# 3_DDR3.net
KiCad netlist of a schematic drawn in Altium Designer
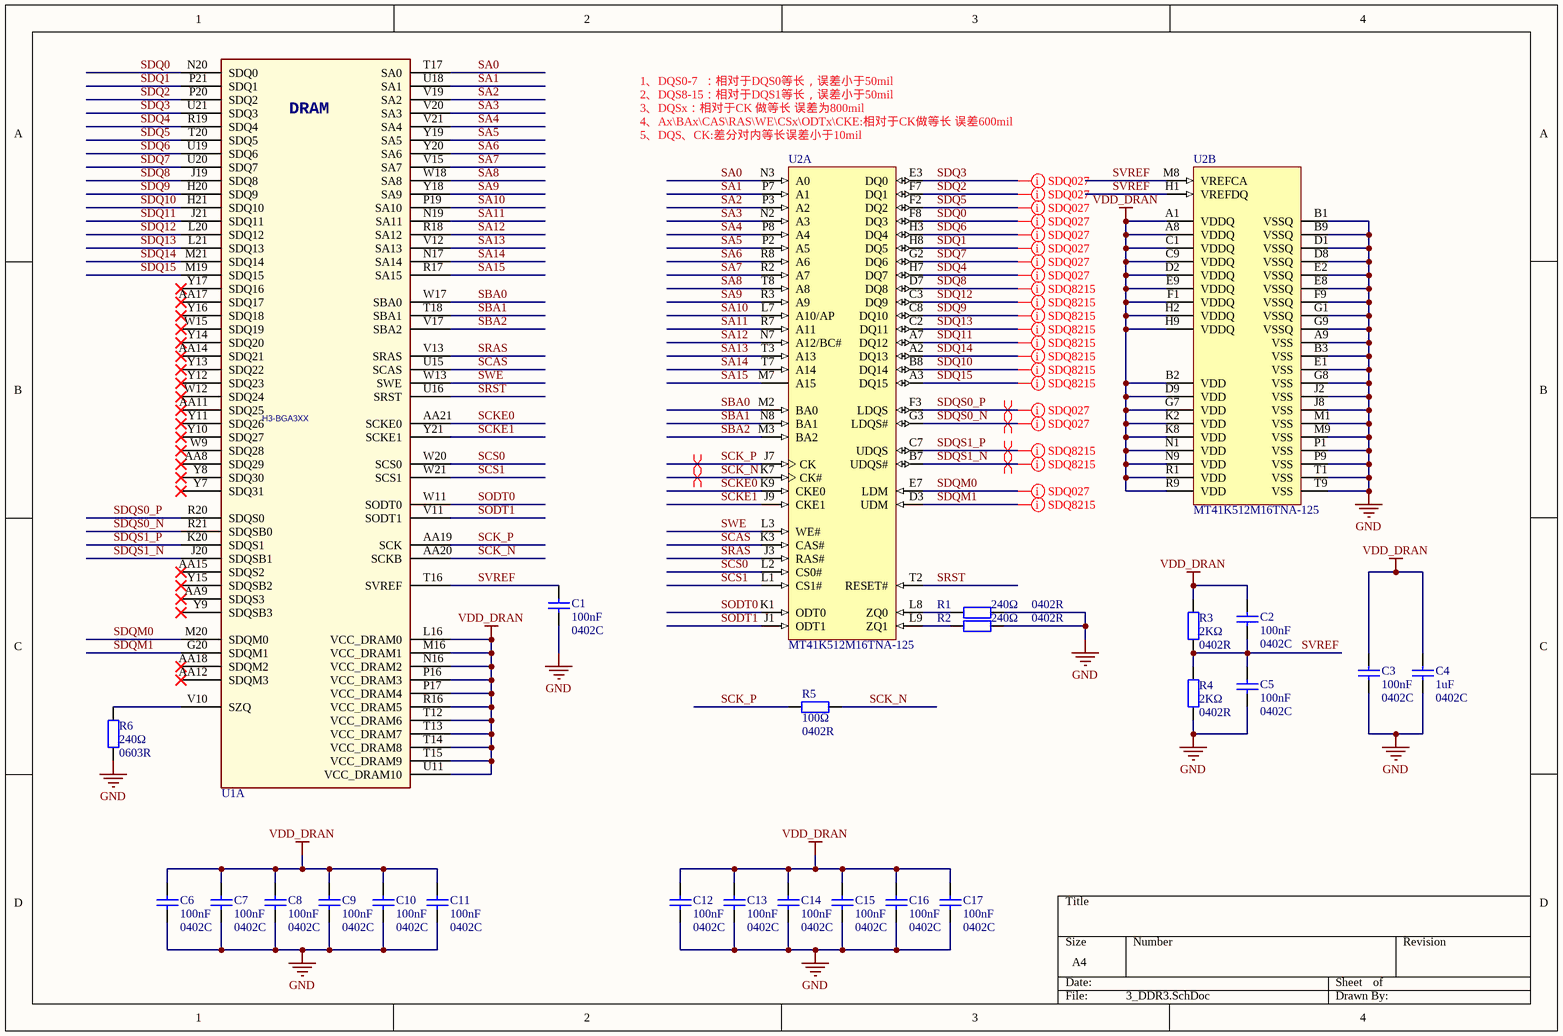
[diagram p0: 3_DDR3.SchDoc]

(export (version "E")
  (design (tool "Eeschema 10.0.6"))
  (components
    (comp (ref "C1")
      (value "100nF")
      (footprint "0402_C")
      (description "贴片电容")
      (fields (field (name "PACKAGE") "0402C"))
      (libsource (lib "Miscellaneous Devices LC") (part "0402 1nF (102) 10% 50V"))
    )
    (comp (ref "C2")
      (value "100nF")
      (footprint "0402_C")
      (description "贴片电容")
      (fields (field (name "PACKAGE") "0402C"))
      (libsource (lib "Miscellaneous Devices LC") (part "0402 1nF (102) 10% 50V"))
    )
    (comp (ref "C3")
      (value "100nF")
      (footprint "0402_C")
      (description "贴片电容")
      (fields (field (name "PACKAGE") "0402C"))
      (libsource (lib "Miscellaneous Devices LC") (part "0402 1nF (102) 10% 50V"))
    )
    (comp (ref "C4")
      (value "1uF")
      (footprint "0402_C")
      (description "贴片电容")
      (fields (field (name "PACKAGE") "0402C"))
      (libsource (lib "Miscellaneous Devices LC") (part "0402 1nF (102) 10% 50V"))
    )
    (comp (ref "C5")
      (value "100nF")
      (footprint "0402_C")
      (description "贴片电容")
      (fields (field (name "PACKAGE") "0402C"))
      (libsource (lib "Miscellaneous Devices LC") (part "0402 1nF (102) 10% 50V"))
    )
    (comp (ref "C6")
      (value "100nF")
      (footprint "0402_C")
      (description "贴片电容")
      (fields (field (name "PACKAGE") "0402C"))
      (libsource (lib "Miscellaneous Devices LC") (part "0402 1nF (102) 10% 50V"))
    )
    (comp (ref "C7")
      (value "100nF")
      (footprint "0402_C")
      (description "贴片电容")
      (fields (field (name "PACKAGE") "0402C"))
      (libsource (lib "Miscellaneous Devices LC") (part "0402 1nF (102) 10% 50V"))
    )
    (comp (ref "C8")
      (value "100nF")
      (footprint "0402_C")
      (description "贴片电容")
      (fields (field (name "PACKAGE") "0402C"))
      (libsource (lib "Miscellaneous Devices LC") (part "0402 1nF (102) 10% 50V"))
    )
    (comp (ref "C9")
      (value "100nF")
      (footprint "0402_C")
      (description "贴片电容")
      (fields (field (name "PACKAGE") "0402C"))
      (libsource (lib "Miscellaneous Devices LC") (part "0402 1nF (102) 10% 50V"))
    )
    (comp (ref "C10")
      (value "100nF")
      (footprint "0402_C")
      (description "贴片电容")
      (fields (field (name "PACKAGE") "0402C"))
      (libsource (lib "Miscellaneous Devices LC") (part "0402 1nF (102) 10% 50V"))
    )
    (comp (ref "C11")
      (value "100nF")
      (footprint "0402_C")
      (description "贴片电容")
      (fields (field (name "PACKAGE") "0402C"))
      (libsource (lib "Miscellaneous Devices LC") (part "0402 1nF (102) 10% 50V"))
    )
    (comp (ref "C12")
      (value "100nF")
      (footprint "0402_C")
      (description "贴片电容")
      (fields (field (name "PACKAGE") "0402C"))
      (libsource (lib "Miscellaneous Devices LC") (part "0402 1nF (102) 10% 50V"))
    )
    (comp (ref "C13")
      (value "100nF")
      (footprint "0402_C")
      (description "贴片电容")
      (fields (field (name "PACKAGE") "0402C"))
      (libsource (lib "Miscellaneous Devices LC") (part "0402 1nF (102) 10% 50V"))
    )
    (comp (ref "C14")
      (value "100nF")
      (footprint "0402_C")
      (description "贴片电容")
      (fields (field (name "PACKAGE") "0402C"))
      (libsource (lib "Miscellaneous Devices LC") (part "0402 1nF (102) 10% 50V"))
    )
    (comp (ref "C15")
      (value "100nF")
      (footprint "0402_C")
      (description "贴片电容")
      (fields (field (name "PACKAGE") "0402C"))
      (libsource (lib "Miscellaneous Devices LC") (part "0402 1nF (102) 10% 50V"))
    )
    (comp (ref "C16")
      (value "100nF")
      (footprint "0402_C")
      (description "贴片电容")
      (fields (field (name "PACKAGE") "0402C"))
      (libsource (lib "Miscellaneous Devices LC") (part "0402 1nF (102) 10% 50V"))
    )
    (comp (ref "C17")
      (value "100nF")
      (footprint "0402_C")
      (description "贴片电容")
      (fields (field (name "PACKAGE") "0402C"))
      (libsource (lib "Miscellaneous Devices LC") (part "0402 1nF (102) 10% 50V"))
    )
    (comp (ref "R1")
      (value "240Ω")
      (footprint "0402_R")
      (description "贴片电阻")
      (fields (field (name "PACKAGE") "0402R"))
      (libsource (lib "") (part "0402 1KΩ (1001) 1%_1"))
    )
    (comp (ref "R2")
      (value "240Ω")
      (footprint "0402_R")
      (description "贴片电阻")
      (fields (field (name "PACKAGE") "0402R"))
      (libsource (lib "") (part "0402 1KΩ (1001) 1%_1"))
    )
    (comp (ref "R3")
      (value "2KΩ")
      (footprint "0402_R")
      (description "贴片电阻")
      (fields (field (name "PACKAGE") "0402R"))
      (libsource (lib "Miscellaneous Devices LC") (part "0402 1KΩ (1001) 1%"))
    )
    (comp (ref "R4")
      (value "2KΩ")
      (footprint "0402_R")
      (description "贴片电阻")
      (fields (field (name "PACKAGE") "0402R"))
      (libsource (lib "Miscellaneous Devices LC") (part "0402 1KΩ (1001) 1%"))
    )
    (comp (ref "R5")
      (value "100Ω")
      (footprint "0402_R")
      (description "贴片电阻")
      (fields (field (name "PACKAGE") "0402R"))
      (libsource (lib "") (part "0402 1KΩ (1001) 1%_1"))
    )
    (comp (ref "R6")
      (value "240Ω")
      (footprint "0603_R")
      (description "贴片电阻")
      (fields (field (name "PACKAGE") "0603R"))
      (libsource (lib "") (part "0402 1KΩ (1001) 1%_2"))
    )
    (comp (ref "U1")
      (value "H3-BGA3XX")
      (footprint "BGA347P0_65B14X14")
      (libsource (lib "MAGNET_L") (part "H3-BGA3XX"))
    )
    (comp (ref "U2")
      (value "MT41K512M16TNA-125")
      (footprint "MICT-TNA-96")
      (description "8Gb SDRAM, 512Mb x 16, 1.25ns, 1.35V, 0 to 95 degC, 96-Ball FBGA, Pb-Free")
      (fields (field (name "VOLTAGE") "1.35V?") (field (name "MANUFACTURER") "Micron"))
      (libsource (lib "Micron Memory DDR3 SDRAM") (part "MT41K512M16TNA-125"))
    )
  )
  (nets
    (net (code "1") (name "/SA0") (class "Default")
      (node (ref "U1") (pin "T17") (pinfunction "SA0_T17") (pintype "passive"))
      (node (ref "U2") (pin "N3") (pinfunction "A0_N3") (pintype "input"))
    )
    (net (code "2") (name "/SA1") (class "Default")
      (node (ref "U1") (pin "U18") (pinfunction "SA1_U18") (pintype "passive"))
      (node (ref "U2") (pin "P7") (pinfunction "A1_P7") (pintype "input"))
    )
    (net (code "3") (name "/SA2") (class "Default")
      (node (ref "U1") (pin "V19") (pinfunction "SA2_V19") (pintype "passive"))
      (node (ref "U2") (pin "P3") (pinfunction "A2_P3") (pintype "input"))
    )
    (net (code "4") (name "/SA3") (class "Default")
      (node (ref "U1") (pin "V20") (pinfunction "SA3_V20") (pintype "passive"))
      (node (ref "U2") (pin "N2") (pinfunction "A3_N2") (pintype "input"))
    )
    (net (code "5") (name "/SA4") (class "Default")
      (node (ref "U1") (pin "V21") (pinfunction "SA4_V21") (pintype "passive"))
      (node (ref "U2") (pin "P8") (pinfunction "A4_P8") (pintype "input"))
    )
    (net (code "6") (name "/SA5") (class "Default")
      (node (ref "U1") (pin "Y19") (pinfunction "SA5_Y19") (pintype "passive"))
      (node (ref "U2") (pin "P2") (pinfunction "A5_P2") (pintype "input"))
    )
    (net (code "7") (name "/SA6") (class "Default")
      (node (ref "U1") (pin "Y20") (pinfunction "SA6_Y20") (pintype "passive"))
      (node (ref "U2") (pin "R8") (pinfunction "A6_R8") (pintype "input"))
    )
    (net (code "8") (name "/SA7") (class "Default")
      (node (ref "U1") (pin "V15") (pinfunction "SA7_V15") (pintype "passive"))
      (node (ref "U2") (pin "R2") (pinfunction "A7_R2") (pintype "input"))
    )
    (net (code "9") (name "/SA8") (class "Default")
      (node (ref "U1") (pin "W18") (pinfunction "SA8_W18") (pintype "passive"))
      (node (ref "U2") (pin "T8") (pinfunction "A8_T8") (pintype "input"))
    )
    (net (code "10") (name "/SA9") (class "Default")
      (node (ref "U1") (pin "Y18") (pinfunction "SA9_Y18") (pintype "passive"))
      (node (ref "U2") (pin "R3") (pinfunction "A9_R3") (pintype "input"))
    )
    (net (code "11") (name "/SA10") (class "Default")
      (node (ref "U1") (pin "P19") (pinfunction "SA10_P19") (pintype "passive"))
      (node (ref "U2") (pin "L7") (pinfunction "A10/AP_L7") (pintype "input"))
    )
    (net (code "12") (name "/SA11") (class "Default")
      (node (ref "U1") (pin "N19") (pinfunction "SA11_N19") (pintype "passive"))
      (node (ref "U2") (pin "R7") (pinfunction "A11_R7") (pintype "input"))
    )
    (net (code "13") (name "/SA12") (class "Default")
      (node (ref "U1") (pin "R18") (pinfunction "SA12_R18") (pintype "passive"))
      (node (ref "U2") (pin "N7") (pinfunction "A12/BC#_N7") (pintype "input"))
    )
    (net (code "14") (name "/SA13") (class "Default")
      (node (ref "U1") (pin "V12") (pinfunction "SA13_V12") (pintype "passive"))
      (node (ref "U2") (pin "T3") (pinfunction "A13_T3") (pintype "input"))
    )
    (net (code "15") (name "/SA14") (class "Default")
      (node (ref "U1") (pin "N17") (pinfunction "SA14_N17") (pintype "passive"))
      (node (ref "U2") (pin "T7") (pinfunction "A14_T7") (pintype "input"))
    )
    (net (code "16") (name "/SA15") (class "Default")
      (node (ref "U1") (pin "R17") (pinfunction "SA15_R17") (pintype "passive"))
      (node (ref "U2") (pin "M7") (pinfunction "A15_M7") (pintype "passive"))
    )
    (net (code "17") (name "/SBA0") (class "Default")
      (node (ref "U1") (pin "W17") (pinfunction "SBA0_W17") (pintype "passive"))
      (node (ref "U2") (pin "M2") (pinfunction "BA0_M2") (pintype "input"))
    )
    (net (code "18") (name "/SBA1") (class "Default")
      (node (ref "U1") (pin "T18") (pinfunction "SBA1_T18") (pintype "passive"))
      (node (ref "U2") (pin "N8") (pinfunction "BA1_N8") (pintype "input"))
    )
    (net (code "19") (name "/SBA2") (class "Default")
      (node (ref "U1") (pin "V17") (pinfunction "SBA2_V17") (pintype "passive"))
      (node (ref "U2") (pin "M3") (pinfunction "BA2_M3") (pintype "input"))
    )
    (net (code "20") (name "/SCAS") (class "Default")
      (node (ref "U1") (pin "U15") (pinfunction "SCAS_U15") (pintype "passive"))
      (node (ref "U2") (pin "K3") (pinfunction "CAS#_K3") (pintype "input"))
    )
    (net (code "21") (name "/SCKE0") (class "Default")
      (node (ref "U1") (pin "AA21") (pinfunction "SCKE0_AA21") (pintype "passive"))
      (node (ref "U2") (pin "K9") (pinfunction "CKE0_K9") (pintype "input"))
    )
    (net (code "22") (name "/SCKE1") (class "Default")
      (node (ref "U1") (pin "Y21") (pinfunction "SCKE1_Y21") (pintype "passive"))
      (node (ref "U2") (pin "J9") (pinfunction "CKE1_J9") (pintype "input"))
    )
    (net (code "23") (name "/SCK_N") (class "Default")
      (node (ref "R5") (pin "1") (pinfunction "1_1") (pintype "passive"))
      (node (ref "U1") (pin "AA20") (pinfunction "SCKB_AA20") (pintype "passive"))
      (node (ref "U2") (pin "K7") (pinfunction "CK#_K7") (pintype "input"))
    )
    (net (code "24") (name "/SCK_P") (class "Default")
      (node (ref "R5") (pin "2") (pinfunction "2_2") (pintype "passive"))
      (node (ref "U1") (pin "AA19") (pinfunction "SCK_AA19") (pintype "passive"))
      (node (ref "U2") (pin "J7") (pinfunction "CK_J7") (pintype "input"))
    )
    (net (code "25") (name "/SCS0") (class "Default")
      (node (ref "U1") (pin "W20") (pinfunction "SCS0_W20") (pintype "passive"))
      (node (ref "U2") (pin "L2") (pinfunction "CS0#_L2") (pintype "input"))
    )
    (net (code "26") (name "/SCS1") (class "Default")
      (node (ref "U1") (pin "W21") (pinfunction "SCS1_W21") (pintype "passive"))
      (node (ref "U2") (pin "L1") (pinfunction "CS1#_L1") (pintype "input"))
    )
    (net (code "27") (name "/SDQ0") (class "Default")
      (node (ref "U1") (pin "N20") (pinfunction "SDQ0_N20") (pintype "passive"))
      (node (ref "U2") (pin "F8") (pinfunction "DQ3_F8") (pintype "bidirectional"))
    )
    (net (code "28") (name "/SDQ1") (class "Default")
      (node (ref "U1") (pin "P21") (pinfunction "SDQ1_P21") (pintype "passive"))
      (node (ref "U2") (pin "H8") (pinfunction "DQ5_H8") (pintype "bidirectional"))
    )
    (net (code "29") (name "/SDQ2") (class "Default")
      (node (ref "U1") (pin "P20") (pinfunction "SDQ2_P20") (pintype "passive"))
      (node (ref "U2") (pin "F7") (pinfunction "DQ1_F7") (pintype "bidirectional"))
    )
    (net (code "30") (name "/SDQ3") (class "Default")
      (node (ref "U1") (pin "U21") (pinfunction "SDQ3_U21") (pintype "passive"))
      (node (ref "U2") (pin "E3") (pinfunction "DQ0_E3") (pintype "bidirectional"))
    )
    (net (code "31") (name "/SDQ4") (class "Default")
      (node (ref "U1") (pin "R19") (pinfunction "SDQ4_R19") (pintype "passive"))
      (node (ref "U2") (pin "H7") (pinfunction "DQ7_H7") (pintype "bidirectional"))
    )
    (net (code "32") (name "/SDQ5") (class "Default")
      (node (ref "U1") (pin "T20") (pinfunction "SDQ5_T20") (pintype "passive"))
      (node (ref "U2") (pin "F2") (pinfunction "DQ2_F2") (pintype "bidirectional"))
    )
    (net (code "33") (name "/SDQ6") (class "Default")
      (node (ref "U1") (pin "U19") (pinfunction "SDQ6_U19") (pintype "passive"))
      (node (ref "U2") (pin "H3") (pinfunction "DQ4_H3") (pintype "bidirectional"))
    )
    (net (code "34") (name "/SDQ7") (class "Default")
      (node (ref "U1") (pin "U20") (pinfunction "SDQ7_U20") (pintype "passive"))
      (node (ref "U2") (pin "G2") (pinfunction "DQ6_G2") (pintype "bidirectional"))
    )
    (net (code "35") (name "/SDQ8") (class "Default")
      (node (ref "U1") (pin "J19") (pinfunction "SDQ8_J19") (pintype "passive"))
      (node (ref "U2") (pin "D7") (pinfunction "DQ8_D7") (pintype "bidirectional"))
    )
    (net (code "36") (name "/SDQ9") (class "Default")
      (node (ref "U1") (pin "H20") (pinfunction "SDQ9_H20") (pintype "passive"))
      (node (ref "U2") (pin "C8") (pinfunction "DQ10_C8") (pintype "bidirectional"))
    )
    (net (code "37") (name "/SDQ10") (class "Default")
      (node (ref "U1") (pin "H21") (pinfunction "SDQ10_H21") (pintype "passive"))
      (node (ref "U2") (pin "B8") (pinfunction "DQ14_B8") (pintype "bidirectional"))
    )
    (net (code "38") (name "/SDQ11") (class "Default")
      (node (ref "U1") (pin "J21") (pinfunction "SDQ11_J21") (pintype "passive"))
      (node (ref "U2") (pin "A7") (pinfunction "DQ12_A7") (pintype "bidirectional"))
    )
    (net (code "39") (name "/SDQ12") (class "Default")
      (node (ref "U1") (pin "L20") (pinfunction "SDQ12_L20") (pintype "passive"))
      (node (ref "U2") (pin "C3") (pinfunction "DQ9_C3") (pintype "bidirectional"))
    )
    (net (code "40") (name "/SDQ13") (class "Default")
      (node (ref "U1") (pin "L21") (pinfunction "SDQ13_L21") (pintype "passive"))
      (node (ref "U2") (pin "C2") (pinfunction "DQ11_C2") (pintype "bidirectional"))
    )
    (net (code "41") (name "/SDQ14") (class "Default")
      (node (ref "U1") (pin "M21") (pinfunction "SDQ14_M21") (pintype "passive"))
      (node (ref "U2") (pin "A2") (pinfunction "DQ13_A2") (pintype "bidirectional"))
    )
    (net (code "42") (name "/SDQ15") (class "Default")
      (node (ref "U1") (pin "M19") (pinfunction "SDQ15_M19") (pintype "passive"))
      (node (ref "U2") (pin "A3") (pinfunction "DQ15_A3") (pintype "bidirectional"))
    )
    (net (code "43") (name "/SDQM0") (class "Default")
      (node (ref "U1") (pin "M20") (pinfunction "SDQM0_M20") (pintype "passive"))
      (node (ref "U2") (pin "E7") (pinfunction "LDM_E7") (pintype "input"))
    )
    (net (code "44") (name "/SDQM1") (class "Default")
      (node (ref "U1") (pin "G20") (pinfunction "SDQM1_G20") (pintype "passive"))
      (node (ref "U2") (pin "D3") (pinfunction "UDM_D3") (pintype "input"))
    )
    (net (code "45") (name "/SDQS0_N") (class "Default")
      (node (ref "U1") (pin "R21") (pinfunction "SDQSB0_R21") (pintype "passive"))
      (node (ref "U2") (pin "G3") (pinfunction "LDQS#_G3") (pintype "bidirectional"))
    )
    (net (code "46") (name "/SDQS0_P") (class "Default")
      (node (ref "U1") (pin "R20") (pinfunction "SDQS0_R20") (pintype "passive"))
      (node (ref "U2") (pin "F3") (pinfunction "LDQS_F3") (pintype "bidirectional"))
    )
    (net (code "47") (name "/SDQS1_N") (class "Default")
      (node (ref "U1") (pin "J20") (pinfunction "SDQSB1_J20") (pintype "passive"))
      (node (ref "U2") (pin "B7") (pinfunction "UDQS#_B7") (pintype "bidirectional"))
    )
    (net (code "48") (name "/SDQS1_P") (class "Default")
      (node (ref "U1") (pin "K20") (pinfunction "SDQS1_K20") (pintype "passive"))
      (node (ref "U2") (pin "C7") (pinfunction "UDQS_C7") (pintype "bidirectional"))
    )
    (net (code "49") (name "/SODT0") (class "Default")
      (node (ref "U1") (pin "W11") (pinfunction "SODT0_W11") (pintype "passive"))
      (node (ref "U2") (pin "K1") (pinfunction "ODT0_K1") (pintype "input"))
    )
    (net (code "50") (name "/SODT1") (class "Default")
      (node (ref "U1") (pin "V11") (pinfunction "SODT1_V11") (pintype "passive"))
      (node (ref "U2") (pin "J1") (pinfunction "ODT1_J1") (pintype "input"))
    )
    (net (code "51") (name "/SRAS") (class "Default")
      (node (ref "U1") (pin "V13") (pinfunction "SRAS_V13") (pintype "passive"))
      (node (ref "U2") (pin "J3") (pinfunction "RAS#_J3") (pintype "input"))
    )
    (net (code "52") (name "/SRST") (class "Default")
      (node (ref "U1") (pin "U16") (pinfunction "SRST_U16") (pintype "passive"))
      (node (ref "U2") (pin "T2") (pinfunction "RESET#_T2") (pintype "input"))
    )
    (net (code "53") (name "/SVREF") (class "Default")
      (node (ref "C1") (pin "2") (pinfunction "2_2") (pintype "passive"))
      (node (ref "C2") (pin "1") (pinfunction "1_1") (pintype "passive"))
      (node (ref "C5") (pin "2") (pinfunction "2_2") (pintype "passive"))
      (node (ref "R3") (pin "2") (pinfunction "2_2") (pintype "passive"))
      (node (ref "R4") (pin "1") (pinfunction "1_1") (pintype "passive"))
      (node (ref "U1") (pin "T16") (pinfunction "SVREF_T16") (pintype "passive"))
      (node (ref "U2") (pin "H1") (pinfunction "VREFDQ_H1") (pintype "input"))
      (node (ref "U2") (pin "M8") (pinfunction "VREFCA_M8") (pintype "input"))
    )
    (net (code "54") (name "/SWE") (class "Default")
      (node (ref "U1") (pin "W13") (pinfunction "SWE_W13") (pintype "passive"))
      (node (ref "U2") (pin "L3") (pinfunction "WE#_L3") (pintype "input"))
    )
    (net (code "55") (name "GND") (class "Default")
      (node (ref "C1") (pin "1") (pinfunction "1_1") (pintype "passive"))
      (node (ref "C10") (pin "1") (pinfunction "1_1") (pintype "passive"))
      (node (ref "C11") (pin "1") (pinfunction "1_1") (pintype "passive"))
      (node (ref "C12") (pin "1") (pinfunction "1_1") (pintype "passive"))
      (node (ref "C13") (pin "1") (pinfunction "1_1") (pintype "passive"))
      (node (ref "C14") (pin "1") (pinfunction "1_1") (pintype "passive"))
      (node (ref "C15") (pin "1") (pinfunction "1_1") (pintype "passive"))
      (node (ref "C16") (pin "1") (pinfunction "1_1") (pintype "passive"))
      (node (ref "C17") (pin "1") (pinfunction "1_1") (pintype "passive"))
      (node (ref "C3") (pin "1") (pinfunction "1_1") (pintype "passive"))
      (node (ref "C4") (pin "1") (pinfunction "1_1") (pintype "passive"))
      (node (ref "C5") (pin "1") (pinfunction "1_1") (pintype "passive"))
      (node (ref "C6") (pin "1") (pinfunction "1_1") (pintype "passive"))
      (node (ref "C7") (pin "1") (pinfunction "1_1") (pintype "passive"))
      (node (ref "C8") (pin "1") (pinfunction "1_1") (pintype "passive"))
      (node (ref "C9") (pin "1") (pinfunction "1_1") (pintype "passive"))
      (node (ref "R1") (pin "1") (pinfunction "1_1") (pintype "passive"))
      (node (ref "R2") (pin "1") (pinfunction "1_1") (pintype "passive"))
      (node (ref "R4") (pin "2") (pinfunction "2_2") (pintype "passive"))
      (node (ref "R6") (pin "1") (pinfunction "1_1") (pintype "passive"))
      (node (ref "U2") (pin "A9") (pinfunction "VSS_A9") (pintype "power_in"))
      (node (ref "U2") (pin "B1") (pinfunction "VSSQ_B1") (pintype "power_in"))
      (node (ref "U2") (pin "B3") (pinfunction "VSS_B3") (pintype "power_in"))
      (node (ref "U2") (pin "B9") (pinfunction "VSSQ_B9") (pintype "power_in"))
      (node (ref "U2") (pin "D1") (pinfunction "VSSQ_D1") (pintype "power_in"))
      (node (ref "U2") (pin "D8") (pinfunction "VSSQ_D8") (pintype "power_in"))
      (node (ref "U2") (pin "E1") (pinfunction "VSS_E1") (pintype "power_in"))
      (node (ref "U2") (pin "E2") (pinfunction "VSSQ_E2") (pintype "power_in"))
      (node (ref "U2") (pin "E8") (pinfunction "VSSQ_E8") (pintype "power_in"))
      (node (ref "U2") (pin "F9") (pinfunction "VSSQ_F9") (pintype "power_in"))
      (node (ref "U2") (pin "G1") (pinfunction "VSSQ_G1") (pintype "power_in"))
      (node (ref "U2") (pin "G8") (pinfunction "VSS_G8") (pintype "power_in"))
      (node (ref "U2") (pin "G9") (pinfunction "VSSQ_G9") (pintype "power_in"))
      (node (ref "U2") (pin "J2") (pinfunction "VSS_J2") (pintype "power_in"))
      (node (ref "U2") (pin "J8") (pinfunction "VSS_J8") (pintype "power_in"))
      (node (ref "U2") (pin "M1") (pinfunction "VSS_M1") (pintype "power_in"))
      (node (ref "U2") (pin "M9") (pinfunction "VSS_M9") (pintype "power_in"))
      (node (ref "U2") (pin "P1") (pinfunction "VSS_P1") (pintype "power_in"))
      (node (ref "U2") (pin "P9") (pinfunction "VSS_P9") (pintype "power_in"))
      (node (ref "U2") (pin "T1") (pinfunction "VSS_T1") (pintype "power_in"))
      (node (ref "U2") (pin "T9") (pinfunction "VSS_T9") (pintype "power_in"))
    )
    (net (code "56") (name "Net-(U1A-SZQ)") (class "Default")
      (node (ref "R6") (pin "2") (pinfunction "2_2") (pintype "passive"))
      (node (ref "U1") (pin "V10") (pinfunction "SZQ_V10") (pintype "passive"))
    )
    (net (code "57") (name "Net-(U2A-ZQ0)") (class "Default")
      (node (ref "R1") (pin "2") (pinfunction "2_2") (pintype "passive"))
      (node (ref "U2") (pin "L8") (pinfunction "ZQ0_L8") (pintype "input"))
    )
    (net (code "58") (name "Net-(U2A-ZQ1)") (class "Default")
      (node (ref "R2") (pin "2") (pinfunction "2_2") (pintype "passive"))
      (node (ref "U2") (pin "L9") (pinfunction "ZQ1_L9") (pintype "input"))
    )
    (net (code "59") (name "VDD_DRAN") (class "Default")
      (node (ref "C10") (pin "2") (pinfunction "2_2") (pintype "passive"))
      (node (ref "C11") (pin "2") (pinfunction "2_2") (pintype "passive"))
      (node (ref "C12") (pin "2") (pinfunction "2_2") (pintype "passive"))
      (node (ref "C13") (pin "2") (pinfunction "2_2") (pintype "passive"))
      (node (ref "C14") (pin "2") (pinfunction "2_2") (pintype "passive"))
      (node (ref "C15") (pin "2") (pinfunction "2_2") (pintype "passive"))
      (node (ref "C16") (pin "2") (pinfunction "2_2") (pintype "passive"))
      (node (ref "C17") (pin "2") (pinfunction "2_2") (pintype "passive"))
      (node (ref "C2") (pin "2") (pinfunction "2_2") (pintype "passive"))
      (node (ref "C3") (pin "2") (pinfunction "2_2") (pintype "passive"))
      (node (ref "C4") (pin "2") (pinfunction "2_2") (pintype "passive"))
      (node (ref "C6") (pin "2") (pinfunction "2_2") (pintype "passive"))
      (node (ref "C7") (pin "2") (pinfunction "2_2") (pintype "passive"))
      (node (ref "C8") (pin "2") (pinfunction "2_2") (pintype "passive"))
      (node (ref "C9") (pin "2") (pinfunction "2_2") (pintype "passive"))
      (node (ref "R3") (pin "1") (pinfunction "1_1") (pintype "passive"))
      (node (ref "U1") (pin "L16") (pinfunction "VCC_DRAM0_L16") (pintype "passive"))
      (node (ref "U1") (pin "M16") (pinfunction "VCC_DRAM1_M16") (pintype "passive"))
      (node (ref "U1") (pin "N16") (pinfunction "VCC_DRAM2_N16") (pintype "passive"))
      (node (ref "U1") (pin "P16") (pinfunction "VCC_DRAM3_P16") (pintype "passive"))
      (node (ref "U1") (pin "P17") (pinfunction "VCC_DRAM4_P17") (pintype "passive"))
      (node (ref "U1") (pin "R16") (pinfunction "VCC_DRAM5_R16") (pintype "passive"))
      (node (ref "U1") (pin "T12") (pinfunction "VCC_DRAM6_T12") (pintype "passive"))
      (node (ref "U1") (pin "T13") (pinfunction "VCC_DRAM7_T13") (pintype "passive"))
      (node (ref "U1") (pin "T14") (pinfunction "VCC_DRAM8_T14") (pintype "passive"))
      (node (ref "U1") (pin "T15") (pinfunction "VCC_DRAM9_T15") (pintype "passive"))
      (node (ref "U1") (pin "U11") (pinfunction "VCC_DRAM10_U11") (pintype "passive"))
      (node (ref "U2") (pin "A1") (pinfunction "VDDQ_A1") (pintype "power_in"))
      (node (ref "U2") (pin "A8") (pinfunction "VDDQ_A8") (pintype "power_in"))
      (node (ref "U2") (pin "B2") (pinfunction "VDD_B2") (pintype "power_in"))
      (node (ref "U2") (pin "C1") (pinfunction "VDDQ_C1") (pintype "power_in"))
      (node (ref "U2") (pin "C9") (pinfunction "VDDQ_C9") (pintype "power_in"))
      (node (ref "U2") (pin "D2") (pinfunction "VDDQ_D2") (pintype "power_in"))
      (node (ref "U2") (pin "D9") (pinfunction "VDD_D9") (pintype "power_in"))
      (node (ref "U2") (pin "E9") (pinfunction "VDDQ_E9") (pintype "power_in"))
      (node (ref "U2") (pin "F1") (pinfunction "VDDQ_F1") (pintype "power_in"))
      (node (ref "U2") (pin "G7") (pinfunction "VDD_G7") (pintype "power_in"))
      (node (ref "U2") (pin "H2") (pinfunction "VDDQ_H2") (pintype "power_in"))
      (node (ref "U2") (pin "H9") (pinfunction "VDDQ_H9") (pintype "power_in"))
      (node (ref "U2") (pin "K2") (pinfunction "VDD_K2") (pintype "power_in"))
      (node (ref "U2") (pin "K8") (pinfunction "VDD_K8") (pintype "power_in"))
      (node (ref "U2") (pin "N1") (pinfunction "VDD_N1") (pintype "power_in"))
      (node (ref "U2") (pin "N9") (pinfunction "VDD_N9") (pintype "power_in"))
      (node (ref "U2") (pin "R1") (pinfunction "VDD_R1") (pintype "power_in"))
      (node (ref "U2") (pin "R9") (pinfunction "VDD_R9") (pintype "power_in"))
    )
    (net (code "60") (name "unconnected-(U1A-SDQ16-PadY17)") (class "Default")
      (node (ref "U1") (pin "Y17") (pinfunction "SDQ16_Y17") (pintype "passive+no_connect"))
    )
    (net (code "61") (name "unconnected-(U1A-SDQ17-PadAA17)") (class "Default")
      (node (ref "U1") (pin "AA17") (pinfunction "SDQ17_AA17") (pintype "passive+no_connect"))
    )
    (net (code "62") (name "unconnected-(U1A-SDQ18-PadY16)") (class "Default")
      (node (ref "U1") (pin "Y16") (pinfunction "SDQ18_Y16") (pintype "passive+no_connect"))
    )
    (net (code "63") (name "unconnected-(U1A-SDQ19-PadW15)") (class "Default")
      (node (ref "U1") (pin "W15") (pinfunction "SDQ19_W15") (pintype "passive+no_connect"))
    )
    (net (code "64") (name "unconnected-(U1A-SDQ20-PadY14)") (class "Default")
      (node (ref "U1") (pin "Y14") (pinfunction "SDQ20_Y14") (pintype "passive+no_connect"))
    )
    (net (code "65") (name "unconnected-(U1A-SDQ21-PadAA14)") (class "Default")
      (node (ref "U1") (pin "AA14") (pinfunction "SDQ21_AA14") (pintype "passive+no_connect"))
    )
    (net (code "66") (name "unconnected-(U1A-SDQ22-PadY13)") (class "Default")
      (node (ref "U1") (pin "Y13") (pinfunction "SDQ22_Y13") (pintype "passive+no_connect"))
    )
    (net (code "67") (name "unconnected-(U1A-SDQ23-PadY12)") (class "Default")
      (node (ref "U1") (pin "Y12") (pinfunction "SDQ23_Y12") (pintype "passive+no_connect"))
    )
    (net (code "68") (name "unconnected-(U1A-SDQ24-PadW12)") (class "Default")
      (node (ref "U1") (pin "W12") (pinfunction "SDQ24_W12") (pintype "passive+no_connect"))
    )
    (net (code "69") (name "unconnected-(U1A-SDQ25-PadAA11)") (class "Default")
      (node (ref "U1") (pin "AA11") (pinfunction "SDQ25_AA11") (pintype "passive+no_connect"))
    )
    (net (code "70") (name "unconnected-(U1A-SDQ26-PadY11)") (class "Default")
      (node (ref "U1") (pin "Y11") (pinfunction "SDQ26_Y11") (pintype "passive+no_connect"))
    )
    (net (code "71") (name "unconnected-(U1A-SDQ27-PadY10)") (class "Default")
      (node (ref "U1") (pin "Y10") (pinfunction "SDQ27_Y10") (pintype "passive+no_connect"))
    )
    (net (code "72") (name "unconnected-(U1A-SDQ28-PadW9)") (class "Default")
      (node (ref "U1") (pin "W9") (pinfunction "SDQ28_W9") (pintype "passive+no_connect"))
    )
    (net (code "73") (name "unconnected-(U1A-SDQ29-PadAA8)") (class "Default")
      (node (ref "U1") (pin "AA8") (pinfunction "SDQ29_AA8") (pintype "passive+no_connect"))
    )
    (net (code "74") (name "unconnected-(U1A-SDQ30-PadY8)") (class "Default")
      (node (ref "U1") (pin "Y8") (pinfunction "SDQ30_Y8") (pintype "passive+no_connect"))
    )
    (net (code "75") (name "unconnected-(U1A-SDQ31-PadY7)") (class "Default")
      (node (ref "U1") (pin "Y7") (pinfunction "SDQ31_Y7") (pintype "passive+no_connect"))
    )
    (net (code "76") (name "unconnected-(U1A-SDQM2-PadAA18)") (class "Default")
      (node (ref "U1") (pin "AA18") (pinfunction "SDQM2_AA18") (pintype "passive+no_connect"))
    )
    (net (code "77") (name "unconnected-(U1A-SDQM3-PadAA12)") (class "Default")
      (node (ref "U1") (pin "AA12") (pinfunction "SDQM3_AA12") (pintype "passive+no_connect"))
    )
    (net (code "78") (name "unconnected-(U1A-SDQS2-PadAA15)") (class "Default")
      (node (ref "U1") (pin "AA15") (pinfunction "SDQS2_AA15") (pintype "passive+no_connect"))
    )
    (net (code "79") (name "unconnected-(U1A-SDQS3-PadAA9)") (class "Default")
      (node (ref "U1") (pin "AA9") (pinfunction "SDQS3_AA9") (pintype "passive+no_connect"))
    )
    (net (code "80") (name "unconnected-(U1A-SDQSB2-PadY15)") (class "Default")
      (node (ref "U1") (pin "Y15") (pinfunction "SDQSB2_Y15") (pintype "passive+no_connect"))
    )
    (net (code "81") (name "unconnected-(U1A-SDQSB3-PadY9)") (class "Default")
      (node (ref "U1") (pin "Y9") (pinfunction "SDQSB3_Y9") (pintype "passive+no_connect"))
    )
  )
)
